# stm32.net
KiCad netlist of a schematic drawn in EAGLE
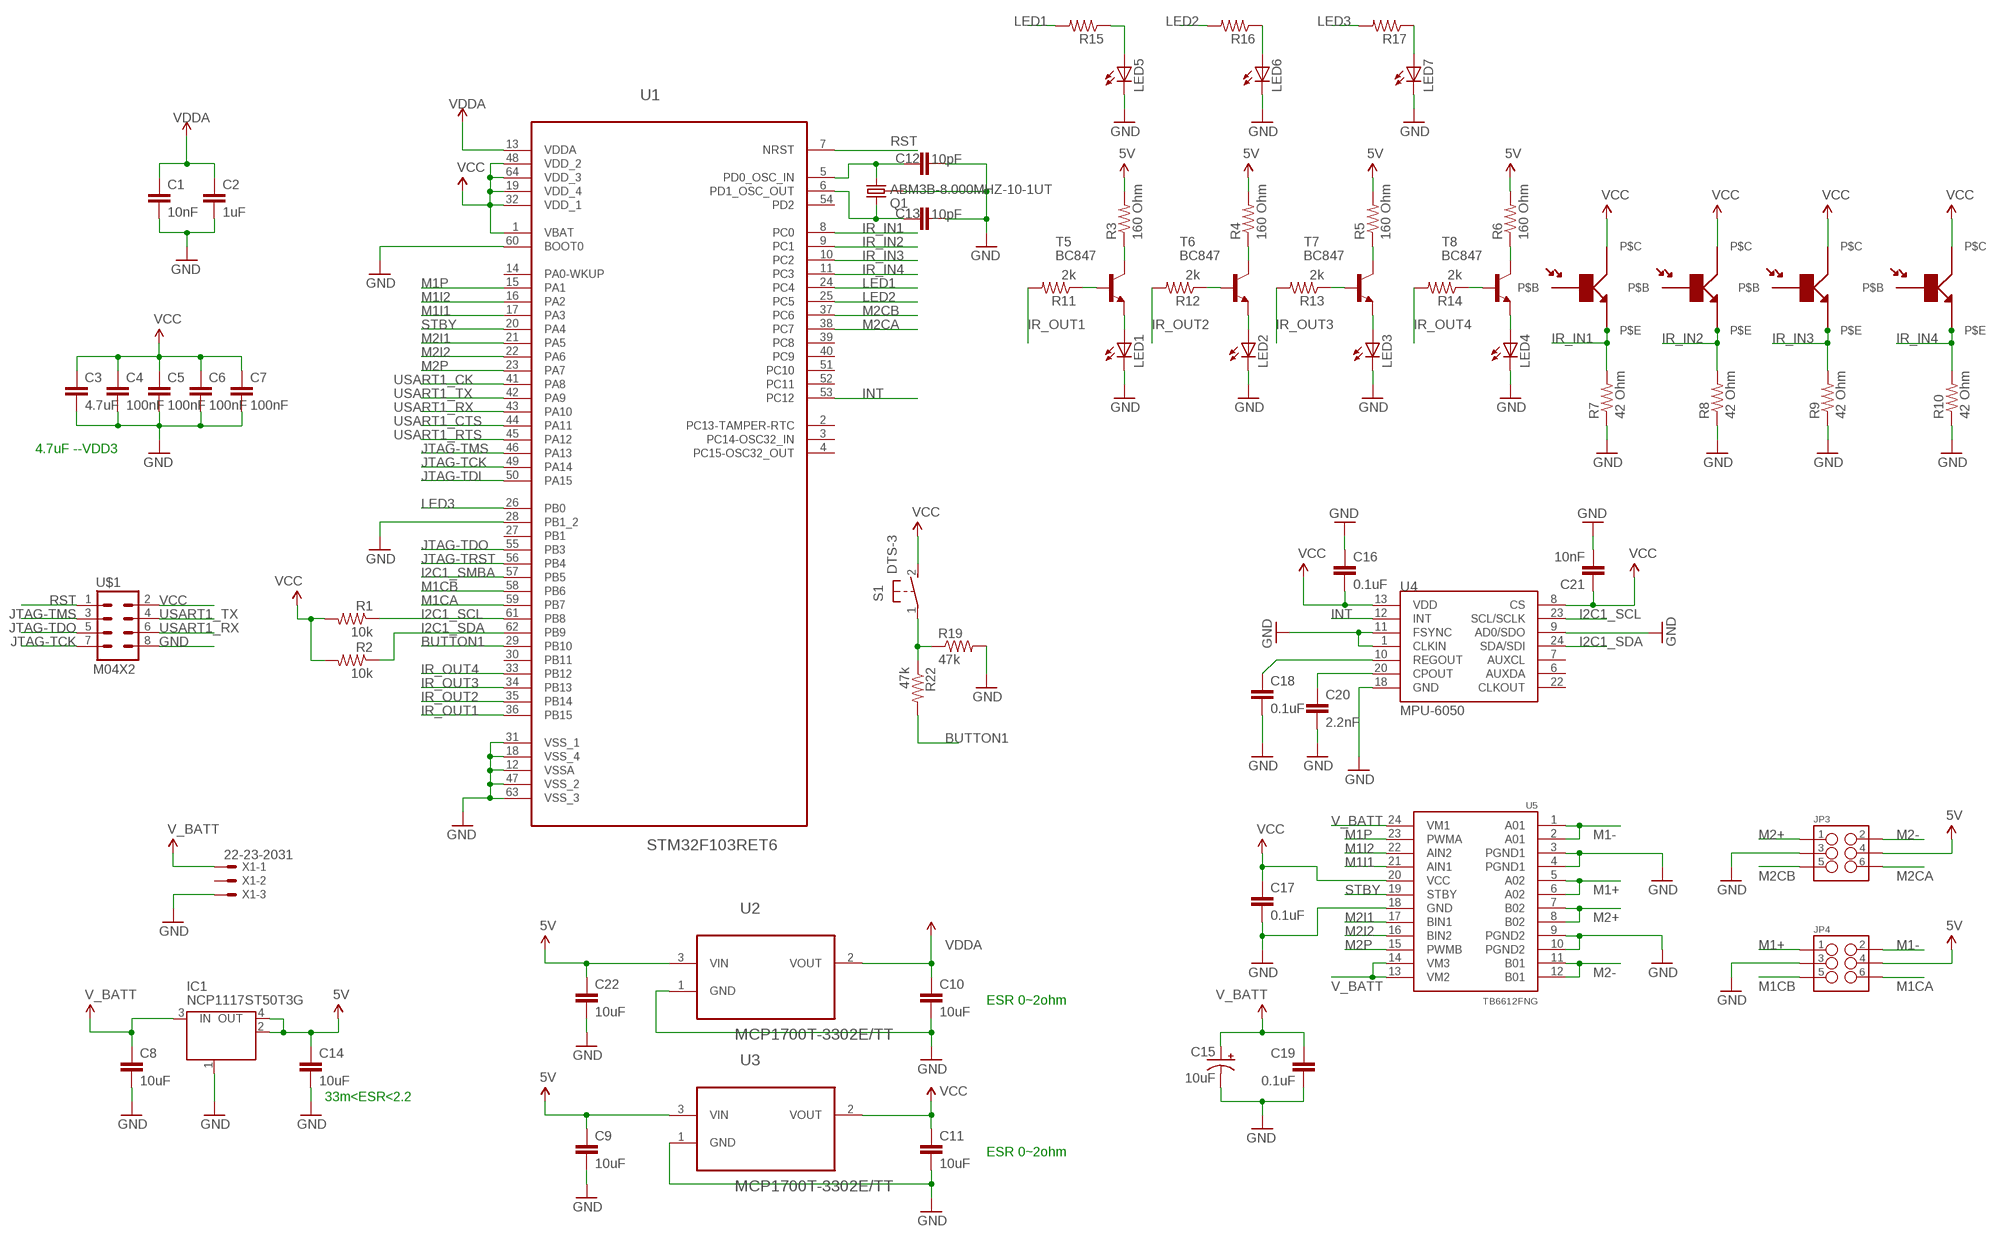
[diagram p0: schematic, sheet 1]

(export (version "E")
  (design (tool "Eeschema 10.0.6"))
  (components
    (comp (ref "C1")
      (value "10nF")
      (footprint "eagle-import:0805")
      (libsource (lib "eagle-import") (part "CAP0805"))
    )
    (comp (ref "C2")
      (value "1uF")
      (footprint "eagle-import:0805")
      (libsource (lib "eagle-import") (part "CAP0805"))
    )
    (comp (ref "C3")
      (value "4.7uF")
      (footprint "eagle-import:0805")
      (libsource (lib "eagle-import") (part "CAP0805"))
    )
    (comp (ref "C4")
      (value "100nF")
      (footprint "eagle-import:0805")
      (libsource (lib "eagle-import") (part "CAP0805"))
    )
    (comp (ref "C5")
      (value "100nF")
      (footprint "eagle-import:0805")
      (libsource (lib "eagle-import") (part "CAP0805"))
    )
    (comp (ref "C6")
      (value "100nF")
      (footprint "eagle-import:0805")
      (libsource (lib "eagle-import") (part "CAP0805"))
    )
    (comp (ref "C7")
      (value "100nF")
      (footprint "eagle-import:0805")
      (libsource (lib "eagle-import") (part "CAP0805"))
    )
    (comp (ref "C8")
      (value "10uF")
      (footprint "eagle-import:0805")
      (libsource (lib "eagle-import") (part "CAP0805"))
    )
    (comp (ref "C9")
      (value "10uF")
      (footprint "eagle-import:0805")
      (libsource (lib "eagle-import") (part "CAP0805"))
    )
    (comp (ref "C10")
      (value "10uF")
      (footprint "eagle-import:0805")
      (libsource (lib "eagle-import") (part "CAP0805"))
    )
    (comp (ref "C11")
      (value "10uF")
      (footprint "eagle-import:0805")
      (libsource (lib "eagle-import") (part "CAP0805"))
    )
    (comp (ref "C12")
      (value "10pF")
      (footprint "eagle-import:0805")
      (libsource (lib "eagle-import") (part "CAP0805"))
    )
    (comp (ref "C13")
      (value "10pF")
      (footprint "eagle-import:0805")
      (libsource (lib "eagle-import") (part "CAP0805"))
    )
    (comp (ref "C14")
      (value "10uF")
      (footprint "eagle-import:0805")
      (libsource (lib "eagle-import") (part "CAP0805"))
    )
    (comp (ref "C15")
      (value "10uF")
      (footprint "eagle-import:EIA3216-KIT")
      (libsource (lib "eagle-import") (part "CAP_POL1206-KIT"))
    )
    (comp (ref "C16")
      (value "0.1uF")
      (footprint "eagle-import:0805")
      (libsource (lib "eagle-import") (part "CAP0805"))
    )
    (comp (ref "C17")
      (value "0.1uF")
      (footprint "eagle-import:0805")
      (libsource (lib "eagle-import") (part "CAP0805"))
    )
    (comp (ref "C18")
      (value "0.1uF")
      (footprint "eagle-import:0805")
      (libsource (lib "eagle-import") (part "CAP0805"))
    )
    (comp (ref "C19")
      (value "0.1uF")
      (footprint "eagle-import:0805")
      (libsource (lib "eagle-import") (part "CAP0805"))
    )
    (comp (ref "C20")
      (value "2.2nF")
      (footprint "eagle-import:0805")
      (libsource (lib "eagle-import") (part "CAP0805"))
    )
    (comp (ref "C21")
      (value "10nF")
      (footprint "eagle-import:0805")
      (libsource (lib "eagle-import") (part "CAP0805"))
    )
    (comp (ref "C22")
      (value "10uF")
      (footprint "eagle-import:0805")
      (libsource (lib "eagle-import") (part "CAP0805"))
    )
    (comp (ref "IC1")
      (value "NCP1117ST50T3G")
      (footprint "eagle-import:SOT223")
      (libsource (lib "eagle-import") (part "MC33269ST-3.3T3"))
    )
    (comp (ref "JP3")
      (value "M03X2NO_SILK")
      (footprint "eagle-import:2X3-NS")
      (libsource (lib "eagle-import") (part "M03X2NO_SILK"))
    )
    (comp (ref "JP4")
      (value "M03X2NO_SILK")
      (footprint "eagle-import:2X3-NS")
      (libsource (lib "eagle-import") (part "M03X2NO_SILK"))
    )
    (comp (ref "LED1")
      (value "LED5MM")
      (footprint "eagle-import:LED5MM")
      (libsource (lib "eagle-import") (part "LED5MM"))
    )
    (comp (ref "LED2")
      (value "LED5MM")
      (footprint "eagle-import:LED5MM")
      (libsource (lib "eagle-import") (part "LED5MM"))
    )
    (comp (ref "LED3")
      (value "LED5MM")
      (footprint "eagle-import:LED5MM")
      (libsource (lib "eagle-import") (part "LED5MM"))
    )
    (comp (ref "LED4")
      (value "LED5MM")
      (footprint "eagle-import:LED5MM")
      (libsource (lib "eagle-import") (part "LED5MM"))
    )
    (comp (ref "LED5")
      (value "LEDSML0805")
      (footprint "eagle-import:SML0805")
      (libsource (lib "eagle-import") (part "LEDSML0805"))
    )
    (comp (ref "LED6")
      (value "LEDSML0805")
      (footprint "eagle-import:SML0805")
      (libsource (lib "eagle-import") (part "LEDSML0805"))
    )
    (comp (ref "LED7")
      (value "LEDSML0805")
      (footprint "eagle-import:SML0805")
      (libsource (lib "eagle-import") (part "LEDSML0805"))
    )
    (comp (ref "Q1")
      (value "ABM3B-8.000MHZ-10-1UT")
      (footprint "eagle-import:CRYSTAL-SMD-5X3")
      (libsource (lib "eagle-import") (part "CRYSTAL-GROUNDED"))
    )
    (comp (ref "R1")
      (value "10k")
      (footprint "eagle-import:0805")
      (libsource (lib "eagle-import") (part "RESISTOR0805-RES"))
    )
    (comp (ref "R2")
      (value "10k")
      (footprint "eagle-import:0805")
      (libsource (lib "eagle-import") (part "RESISTOR0805-RES"))
    )
    (comp (ref "R3")
      (value "160 Ohm")
      (footprint "eagle-import:0805")
      (libsource (lib "eagle-import") (part "SparkFun-Resistors_RESISTOR0805-RES"))
    )
    (comp (ref "R4")
      (value "160 Ohm")
      (footprint "eagle-import:0805")
      (libsource (lib "eagle-import") (part "SparkFun-Resistors_RESISTOR0805-RES"))
    )
    (comp (ref "R5")
      (value "160 Ohm")
      (footprint "eagle-import:0805")
      (libsource (lib "eagle-import") (part "SparkFun-Resistors_RESISTOR0805-RES"))
    )
    (comp (ref "R6")
      (value "160 Ohm")
      (footprint "eagle-import:0805")
      (libsource (lib "eagle-import") (part "SparkFun-Resistors_RESISTOR0805-RES"))
    )
    (comp (ref "R7")
      (value "42 Ohm")
      (footprint "eagle-import:0805")
      (libsource (lib "eagle-import") (part "SparkFun-Resistors_RESISTOR0805-RES"))
    )
    (comp (ref "R8")
      (value "42 Ohm")
      (footprint "eagle-import:0805")
      (libsource (lib "eagle-import") (part "SparkFun-Resistors_RESISTOR0805-RES"))
    )
    (comp (ref "R9")
      (value "42 Ohm")
      (footprint "eagle-import:0805")
      (libsource (lib "eagle-import") (part "SparkFun-Resistors_RESISTOR0805-RES"))
    )
    (comp (ref "R10")
      (value "42 Ohm")
      (footprint "eagle-import:0805")
      (libsource (lib "eagle-import") (part "SparkFun-Resistors_RESISTOR0805-RES"))
    )
    (comp (ref "R11")
      (value "2k")
      (footprint "eagle-import:0805")
      (libsource (lib "eagle-import") (part "SparkFun-Resistors_RESISTOR0805-RES"))
    )
    (comp (ref "R12")
      (value "2k")
      (footprint "eagle-import:0805")
      (libsource (lib "eagle-import") (part "SparkFun-Resistors_RESISTOR0805-RES"))
    )
    (comp (ref "R13")
      (value "2k")
      (footprint "eagle-import:0805")
      (libsource (lib "eagle-import") (part "SparkFun-Resistors_RESISTOR0805-RES"))
    )
    (comp (ref "R14")
      (value "2k")
      (footprint "eagle-import:0805")
      (libsource (lib "eagle-import") (part "SparkFun-Resistors_RESISTOR0805-RES"))
    )
    (comp (ref "R15")
      (value "RESISTOR0805-RES")
      (footprint "eagle-import:0805")
      (libsource (lib "eagle-import") (part "SparkFun-Resistors_RESISTOR0805-RES"))
    )
    (comp (ref "R16")
      (value "RESISTOR0805-RES")
      (footprint "eagle-import:0805")
      (libsource (lib "eagle-import") (part "SparkFun-Resistors_RESISTOR0805-RES"))
    )
    (comp (ref "R17")
      (value "RESISTOR0805-RES")
      (footprint "eagle-import:0805")
      (libsource (lib "eagle-import") (part "SparkFun-Resistors_RESISTOR0805-RES"))
    )
    (comp (ref "R19")
      (value "47k")
      (footprint "eagle-import:0805")
      (libsource (lib "eagle-import") (part "SparkFun-Resistors_RESISTOR0805-RES"))
    )
    (comp (ref "R22")
      (value "47k")
      (footprint "eagle-import:0805")
      (libsource (lib "eagle-import") (part "SparkFun-Resistors_RESISTOR0805-RES"))
    )
    (comp (ref "S1")
      (value "DTS-3")
      (footprint "eagle-import:DTS-3")
      (libsource (lib "eagle-import") (part "DTS-3"))
    )
    (comp (ref "T5")
      (value "BC847")
      (footprint "eagle-import:SOT23")
      (libsource (lib "eagle-import") (part "BC847"))
    )
    (comp (ref "T6")
      (value "BC847")
      (footprint "eagle-import:SOT23")
      (libsource (lib "eagle-import") (part "BC847"))
    )
    (comp (ref "T7")
      (value "BC847")
      (footprint "eagle-import:SOT23")
      (libsource (lib "eagle-import") (part "BC847"))
    )
    (comp (ref "T8")
      (value "BC847")
      (footprint "eagle-import:SOT23")
      (libsource (lib "eagle-import") (part "BC847"))
    )
    (comp (ref "U$1")
      (value "M04X2")
      (footprint "eagle-import:2X4")
      (libsource (lib "eagle-import") (part "M04X2"))
    )
    (comp (ref "U$2")
      (value "PHTRST")
      (footprint "eagle-import:PHTRST")
      (libsource (lib "eagle-import") (part "PHTRST"))
    )
    (comp (ref "U$3")
      (value "PHTRST")
      (footprint "eagle-import:PHTRST")
      (libsource (lib "eagle-import") (part "PHTRST"))
    )
    (comp (ref "U$4")
      (value "PHTRST")
      (footprint "eagle-import:PHTRST")
      (libsource (lib "eagle-import") (part "PHTRST"))
    )
    (comp (ref "U$5")
      (value "PHTRST")
      (footprint "eagle-import:PHTRST")
      (libsource (lib "eagle-import") (part "PHTRST"))
    )
    (comp (ref "U1")
      (value "STM32F103RET6")
      (footprint "eagle-import:QFP50P1200X1200X160-64N")
      (libsource (lib "eagle-import") (part "STM32F103RET6"))
    )
    (comp (ref "U2")
      (value "MCP1700T-3302E/TT")
      (footprint "eagle-import:SOT95P237X112-3N")
      (libsource (lib "eagle-import") (part "MCP1700T-3302E/TT"))
    )
    (comp (ref "U3")
      (value "MCP1700T-3302E/TT")
      (footprint "eagle-import:SOT95P237X112-3N")
      (libsource (lib "eagle-import") (part "MCP1700T-3302E/TT"))
    )
    (comp (ref "U4")
      (value "MPU-6050")
      (footprint "eagle-import:QFN-24-TESTING")
      (libsource (lib "eagle-import") (part "MPU-6000QFN-24"))
    )
    (comp (ref "U5")
      (value "TB6612FNG")
      (footprint "eagle-import:SSOP24")
      (libsource (lib "eagle-import") (part "TB6612FNG"))
    )
    (comp (ref "X1")
      (value "22-23-2031")
      (footprint "eagle-import:22-23-2031")
      (libsource (lib "eagle-import") (part "22-23-2031"))
    )
  )
  (nets
    (net (code "1") (name "/BUTTON1") (class "Default")
      (node (ref "R22") (pin "2") (pinfunction "2_2") (pintype "passive"))
      (node (ref "U1") (pin "29") (pinfunction "PB10_29") (pintype "bidirectional"))
    )
    (net (code "2") (name "/I2C1_SCL") (class "Default")
      (node (ref "R1") (pin "1") (pinfunction "1_1") (pintype "passive"))
      (node (ref "U1") (pin "61") (pinfunction "PB8_61") (pintype "bidirectional"))
      (node (ref "U4") (pin "23") (pinfunction "SCL/SCLK_23") (pintype "bidirectional"))
    )
    (net (code "3") (name "/I2C1_SDA") (class "Default")
      (node (ref "R2") (pin "1") (pinfunction "1_1") (pintype "passive"))
      (node (ref "U1") (pin "62") (pinfunction "PB9_62") (pintype "bidirectional"))
      (node (ref "U4") (pin "24") (pinfunction "SDA/SDI_24") (pintype "bidirectional"))
    )
    (net (code "4") (name "/I2C1_SMBA") (class "Default")
      (node (ref "U1") (pin "57") (pinfunction "PB5_57") (pintype "bidirectional"))
    )
    (net (code "5") (name "/INT") (class "Default")
      (node (ref "U1") (pin "53") (pinfunction "PC12_53") (pintype "bidirectional"))
      (node (ref "U4") (pin "12") (pinfunction "INT_12") (pintype "bidirectional"))
    )
    (net (code "6") (name "/IR_IN1") (class "Default")
      (node (ref "R7") (pin "2") (pinfunction "2_2") (pintype "passive"))
      (node (ref "U$2") (pin "P$E") (pinfunction "P$E_P$E") (pintype "bidirectional"))
      (node (ref "U1") (pin "8") (pinfunction "PC0_8") (pintype "bidirectional"))
    )
    (net (code "7") (name "/IR_IN2") (class "Default")
      (node (ref "R8") (pin "2") (pinfunction "2_2") (pintype "passive"))
      (node (ref "U$3") (pin "P$E") (pinfunction "P$E_P$E") (pintype "bidirectional"))
      (node (ref "U1") (pin "9") (pinfunction "PC1_9") (pintype "bidirectional"))
    )
    (net (code "8") (name "/IR_IN3") (class "Default")
      (node (ref "R9") (pin "2") (pinfunction "2_2") (pintype "passive"))
      (node (ref "U$4") (pin "P$E") (pinfunction "P$E_P$E") (pintype "bidirectional"))
      (node (ref "U1") (pin "10") (pinfunction "PC2_10") (pintype "bidirectional"))
    )
    (net (code "9") (name "/IR_IN4") (class "Default")
      (node (ref "R10") (pin "2") (pinfunction "2_2") (pintype "passive"))
      (node (ref "U$5") (pin "P$E") (pinfunction "P$E_P$E") (pintype "bidirectional"))
      (node (ref "U1") (pin "11") (pinfunction "PC3_11") (pintype "bidirectional"))
    )
    (net (code "10") (name "/IR_OUT1") (class "Default")
      (node (ref "R11") (pin "2") (pinfunction "2_2") (pintype "passive"))
      (node (ref "U1") (pin "36") (pinfunction "PB15_36") (pintype "bidirectional"))
    )
    (net (code "11") (name "/IR_OUT2") (class "Default")
      (node (ref "R12") (pin "2") (pinfunction "2_2") (pintype "passive"))
      (node (ref "U1") (pin "35") (pinfunction "PB14_35") (pintype "bidirectional"))
    )
    (net (code "12") (name "/IR_OUT3") (class "Default")
      (node (ref "R13") (pin "2") (pinfunction "2_2") (pintype "passive"))
      (node (ref "U1") (pin "34") (pinfunction "PB13_34") (pintype "bidirectional"))
    )
    (net (code "13") (name "/IR_OUT4") (class "Default")
      (node (ref "R14") (pin "2") (pinfunction "2_2") (pintype "passive"))
      (node (ref "U1") (pin "33") (pinfunction "PB12_33") (pintype "bidirectional"))
    )
    (net (code "14") (name "/JTAG-TCK") (class "Default")
      (node (ref "U$1") (pin "7") (pinfunction "7_7") (pintype "passive"))
      (node (ref "U1") (pin "49") (pinfunction "PA14_49") (pintype "bidirectional"))
    )
    (net (code "15") (name "/JTAG-TDI") (class "Default")
      (node (ref "U1") (pin "50") (pinfunction "PA15_50") (pintype "bidirectional"))
    )
    (net (code "16") (name "/JTAG-TDO") (class "Default")
      (node (ref "U$1") (pin "5") (pinfunction "5_5") (pintype "passive"))
      (node (ref "U1") (pin "55") (pinfunction "PB3_55") (pintype "bidirectional"))
    )
    (net (code "17") (name "/JTAG-TMS") (class "Default")
      (node (ref "U$1") (pin "3") (pinfunction "3_3") (pintype "passive"))
      (node (ref "U1") (pin "46") (pinfunction "PA13_46") (pintype "bidirectional"))
    )
    (net (code "18") (name "/JTAG-TRST") (class "Default")
      (node (ref "U1") (pin "56") (pinfunction "PB4_56") (pintype "bidirectional"))
    )
    (net (code "19") (name "/LED1") (class "Default")
      (node (ref "R15") (pin "2") (pinfunction "2_2") (pintype "passive"))
      (node (ref "U1") (pin "24") (pinfunction "PC4_24") (pintype "passive"))
    )
    (net (code "20") (name "/LED2") (class "Default")
      (node (ref "R16") (pin "2") (pinfunction "2_2") (pintype "passive"))
      (node (ref "U1") (pin "25") (pinfunction "PC5_25") (pintype "bidirectional"))
    )
    (net (code "21") (name "/LED3") (class "Default")
      (node (ref "R17") (pin "2") (pinfunction "2_2") (pintype "passive"))
      (node (ref "U1") (pin "26") (pinfunction "PB0_26") (pintype "bidirectional"))
    )
    (net (code "22") (name "/M1+") (class "Default")
      (node (ref "JP4") (pin "1") (pinfunction "1_1") (pintype "bidirectional"))
      (node (ref "U5") (pin "5") (pinfunction "A02_5") (pintype "bidirectional"))
      (node (ref "U5") (pin "6") (pinfunction "A02_6") (pintype "bidirectional"))
    )
    (net (code "23") (name "/M1-") (class "Default")
      (node (ref "JP4") (pin "2") (pinfunction "2_2") (pintype "bidirectional"))
      (node (ref "U5") (pin "1") (pinfunction "A01_1") (pintype "bidirectional"))
      (node (ref "U5") (pin "2") (pinfunction "A01_2") (pintype "bidirectional"))
    )
    (net (code "24") (name "/M1CA") (class "Default")
      (node (ref "JP4") (pin "6") (pinfunction "6_6") (pintype "bidirectional"))
      (node (ref "U1") (pin "59") (pinfunction "PB7_59") (pintype "power_in"))
    )
    (net (code "25") (name "/M1CB") (class "Default")
      (node (ref "JP4") (pin "5") (pinfunction "5_5") (pintype "bidirectional"))
      (node (ref "U1") (pin "58") (pinfunction "PB6_58") (pintype "bidirectional"))
    )
    (net (code "26") (name "/M1I1") (class "Default")
      (node (ref "U1") (pin "17") (pinfunction "PA3_17") (pintype "bidirectional"))
      (node (ref "U5") (pin "21") (pinfunction "AIN1_21") (pintype "bidirectional"))
    )
    (net (code "27") (name "/M1I2") (class "Default")
      (node (ref "U1") (pin "16") (pinfunction "PA2_16") (pintype "bidirectional"))
      (node (ref "U5") (pin "22") (pinfunction "AIN2_22") (pintype "bidirectional"))
    )
    (net (code "28") (name "/M1P") (class "Default")
      (node (ref "U1") (pin "15") (pinfunction "PA1_15") (pintype "bidirectional"))
      (node (ref "U5") (pin "23") (pinfunction "PWMA_23") (pintype "bidirectional"))
    )
    (net (code "29") (name "/M2+") (class "Default")
      (node (ref "JP3") (pin "1") (pinfunction "1_1") (pintype "bidirectional"))
      (node (ref "U5") (pin "7") (pinfunction "B02_7") (pintype "bidirectional"))
      (node (ref "U5") (pin "8") (pinfunction "B02_8") (pintype "bidirectional"))
    )
    (net (code "30") (name "/M2-") (class "Default")
      (node (ref "JP3") (pin "2") (pinfunction "2_2") (pintype "bidirectional"))
      (node (ref "U5") (pin "11") (pinfunction "B01_11") (pintype "bidirectional"))
      (node (ref "U5") (pin "12") (pinfunction "B01_12") (pintype "bidirectional"))
    )
    (net (code "31") (name "/M2CA") (class "Default")
      (node (ref "JP3") (pin "6") (pinfunction "6_6") (pintype "bidirectional"))
      (node (ref "U1") (pin "38") (pinfunction "PC7_38") (pintype "bidirectional"))
    )
    (net (code "32") (name "/M2CB") (class "Default")
      (node (ref "JP3") (pin "5") (pinfunction "5_5") (pintype "bidirectional"))
      (node (ref "U1") (pin "37") (pinfunction "PC6_37") (pintype "bidirectional"))
    )
    (net (code "33") (name "/M2I1") (class "Default")
      (node (ref "U1") (pin "21") (pinfunction "PA5_21") (pintype "bidirectional"))
      (node (ref "U5") (pin "17") (pinfunction "BIN1_17") (pintype "bidirectional"))
    )
    (net (code "34") (name "/M2I2") (class "Default")
      (node (ref "U1") (pin "22") (pinfunction "PA6_22") (pintype "bidirectional"))
      (node (ref "U5") (pin "16") (pinfunction "BIN2_16") (pintype "bidirectional"))
    )
    (net (code "35") (name "/M2P") (class "Default")
      (node (ref "U1") (pin "23") (pinfunction "PA7_23") (pintype "power_in"))
      (node (ref "U5") (pin "15") (pinfunction "PWMB_15") (pintype "bidirectional"))
    )
    (net (code "36") (name "/RST") (class "Default")
      (node (ref "U$1") (pin "1") (pinfunction "1_1") (pintype "passive"))
      (node (ref "U1") (pin "7") (pinfunction "NRST_7") (pintype "output"))
    )
    (net (code "37") (name "/STBY") (class "Default")
      (node (ref "U1") (pin "20") (pinfunction "PA4_20") (pintype "bidirectional"))
      (node (ref "U5") (pin "19") (pinfunction "STBY_19") (pintype "bidirectional"))
    )
    (net (code "38") (name "/USART1_CK") (class "Default")
      (node (ref "U1") (pin "41") (pinfunction "PA8_41") (pintype "bidirectional"))
    )
    (net (code "39") (name "/USART1_CTS") (class "Default")
      (node (ref "U1") (pin "44") (pinfunction "PA11_44") (pintype "bidirectional"))
    )
    (net (code "40") (name "/USART1_RTS") (class "Default")
      (node (ref "U1") (pin "45") (pinfunction "PA12_45") (pintype "bidirectional"))
    )
    (net (code "41") (name "/USART1_RX") (class "Default")
      (node (ref "U$1") (pin "6") (pinfunction "6_6") (pintype "passive"))
      (node (ref "U1") (pin "43") (pinfunction "PA10_43") (pintype "bidirectional"))
    )
    (net (code "42") (name "/USART1_TX") (class "Default")
      (node (ref "U$1") (pin "4") (pinfunction "4_4") (pintype "passive"))
      (node (ref "U1") (pin "42") (pinfunction "PA9_42") (pintype "bidirectional"))
    )
    (net (code "43") (name "5V") (class "Default")
      (node (ref "C14") (pin "1") (pinfunction "1_1") (pintype "passive"))
      (node (ref "C22") (pin "1") (pinfunction "1_1") (pintype "passive"))
      (node (ref "C9") (pin "1") (pinfunction "1_1") (pintype "passive"))
      (node (ref "IC1") (pin "2") (pinfunction "OUT_2") (pintype "passive"))
      (node (ref "IC1") (pin "4") (pinfunction "OUT_4") (pintype "passive"))
      (node (ref "JP3") (pin "4") (pinfunction "4_4") (pintype "bidirectional"))
      (node (ref "JP4") (pin "4") (pinfunction "4_4") (pintype "bidirectional"))
      (node (ref "R3") (pin "2") (pinfunction "2_2") (pintype "passive"))
      (node (ref "R4") (pin "2") (pinfunction "2_2") (pintype "passive"))
      (node (ref "R5") (pin "2") (pinfunction "2_2") (pintype "passive"))
      (node (ref "R6") (pin "2") (pinfunction "2_2") (pintype "passive"))
      (node (ref "U2") (pin "3") (pinfunction "VIN_3") (pintype "input"))
      (node (ref "U3") (pin "3") (pinfunction "VIN_3") (pintype "input"))
    )
    (net (code "44") (name "GND") (class "Default")
      (node (ref "C1") (pin "2") (pinfunction "2_2") (pintype "passive"))
      (node (ref "C10") (pin "2") (pinfunction "2_2") (pintype "passive"))
      (node (ref "C11") (pin "2") (pinfunction "2_2") (pintype "passive"))
      (node (ref "C12") (pin "1") (pinfunction "1_1") (pintype "passive"))
      (node (ref "C13") (pin "1") (pinfunction "1_1") (pintype "passive"))
      (node (ref "C14") (pin "2") (pinfunction "2_2") (pintype "passive"))
      (node (ref "C15") (pin "C") (pinfunction "-_C") (pintype "passive"))
      (node (ref "C16") (pin "1") (pinfunction "1_1") (pintype "passive"))
      (node (ref "C17") (pin "2") (pinfunction "2_2") (pintype "passive"))
      (node (ref "C18") (pin "2") (pinfunction "2_2") (pintype "passive"))
      (node (ref "C19") (pin "2") (pinfunction "2_2") (pintype "passive"))
      (node (ref "C2") (pin "2") (pinfunction "2_2") (pintype "passive"))
      (node (ref "C20") (pin "2") (pinfunction "2_2") (pintype "passive"))
      (node (ref "C21") (pin "2") (pinfunction "2_2") (pintype "passive"))
      (node (ref "C22") (pin "2") (pinfunction "2_2") (pintype "passive"))
      (node (ref "C3") (pin "2") (pinfunction "2_2") (pintype "passive"))
      (node (ref "C4") (pin "2") (pinfunction "2_2") (pintype "passive"))
      (node (ref "C5") (pin "2") (pinfunction "2_2") (pintype "passive"))
      (node (ref "C6") (pin "2") (pinfunction "2_2") (pintype "passive"))
      (node (ref "C7") (pin "2") (pinfunction "2_2") (pintype "passive"))
      (node (ref "C8") (pin "2") (pinfunction "2_2") (pintype "passive"))
      (node (ref "C9") (pin "2") (pinfunction "2_2") (pintype "passive"))
      (node (ref "IC1") (pin "1") (pinfunction "GND/ADJ_1") (pintype "input"))
      (node (ref "JP3") (pin "3") (pinfunction "3_3") (pintype "bidirectional"))
      (node (ref "JP4") (pin "3") (pinfunction "3_3") (pintype "bidirectional"))
      (node (ref "LED1") (pin "K") (pinfunction "C_K") (pintype "passive"))
      (node (ref "LED2") (pin "K") (pinfunction "C_K") (pintype "passive"))
      (node (ref "LED3") (pin "K") (pinfunction "C_K") (pintype "passive"))
      (node (ref "LED4") (pin "K") (pinfunction "C_K") (pintype "passive"))
      (node (ref "LED5") (pin "C") (pinfunction "C_C") (pintype "passive"))
      (node (ref "LED6") (pin "C") (pinfunction "C_C") (pintype "passive"))
      (node (ref "LED7") (pin "C") (pinfunction "C_C") (pintype "passive"))
      (node (ref "Q1") (pin "2") (pinfunction "3_2") (pintype "passive"))
      (node (ref "Q1") (pin "4") (pinfunction "3_4") (pintype "passive"))
      (node (ref "R10") (pin "1") (pinfunction "1_1") (pintype "passive"))
      (node (ref "R19") (pin "2") (pinfunction "2_2") (pintype "passive"))
      (node (ref "R7") (pin "1") (pinfunction "1_1") (pintype "passive"))
      (node (ref "R8") (pin "1") (pinfunction "1_1") (pintype "passive"))
      (node (ref "R9") (pin "1") (pinfunction "1_1") (pintype "passive"))
      (node (ref "U$1") (pin "8") (pinfunction "8_8") (pintype "passive"))
      (node (ref "U1") (pin "12") (pinfunction "VSSA_12") (pintype "passive"))
      (node (ref "U1") (pin "18") (pinfunction "VSS_4_18") (pintype "passive"))
      (node (ref "U1") (pin "28") (pinfunction "PB1_2_28") (pintype "bidirectional"))
      (node (ref "U1") (pin "31") (pinfunction "VSS_1_31") (pintype "passive"))
      (node (ref "U1") (pin "47") (pinfunction "VSS_2_47") (pintype "passive"))
      (node (ref "U1") (pin "60") (pinfunction "BOOT0_60") (pintype "passive"))
      (node (ref "U1") (pin "63") (pinfunction "VSS_3_63") (pintype "passive"))
      (node (ref "U2") (pin "1") (pinfunction "GND_1") (pintype "passive"))
      (node (ref "U3") (pin "1") (pinfunction "GND_1") (pintype "passive"))
      (node (ref "U4") (pin "1") (pinfunction "CLKIN_1") (pintype "bidirectional"))
      (node (ref "U4") (pin "11") (pinfunction "FSYNC_11") (pintype "bidirectional"))
      (node (ref "U4") (pin "18") (pinfunction "GND_18") (pintype "bidirectional"))
      (node (ref "U4") (pin "9") (pinfunction "AD0/SDO_9") (pintype "bidirectional"))
      (node (ref "U5") (pin "10") (pinfunction "PGND2_10") (pintype "bidirectional"))
      (node (ref "U5") (pin "18") (pinfunction "GND_18") (pintype "bidirectional"))
      (node (ref "U5") (pin "3") (pinfunction "PGND1_3") (pintype "bidirectional"))
      (node (ref "U5") (pin "4") (pinfunction "PGND1_4") (pintype "bidirectional"))
      (node (ref "U5") (pin "9") (pinfunction "PGND2_9") (pintype "bidirectional"))
      (node (ref "X1") (pin "3") (pinfunction "S_3") (pintype "passive"))
    )
    (net (code "45") (name "Net-(LED5-PadA)") (class "Default")
      (node (ref "LED5") (pin "A") (pinfunction "A_A") (pintype "passive"))
      (node (ref "R15") (pin "1") (pinfunction "1_1") (pintype "passive"))
    )
    (net (code "46") (name "Net-(LED6-PadA)") (class "Default")
      (node (ref "LED6") (pin "A") (pinfunction "A_A") (pintype "passive"))
      (node (ref "R16") (pin "1") (pinfunction "1_1") (pintype "passive"))
    )
    (net (code "47") (name "Net-(LED7-PadA)") (class "Default")
      (node (ref "LED7") (pin "A") (pinfunction "A_A") (pintype "passive"))
      (node (ref "R17") (pin "1") (pinfunction "1_1") (pintype "passive"))
    )
    (net (code "48") (name "Net-(Q1-1)") (class "Default")
      (node (ref "C12") (pin "2") (pinfunction "2_2") (pintype "passive"))
      (node (ref "Q1") (pin "3") (pinfunction "1_3") (pintype "passive"))
      (node (ref "U1") (pin "5") (pinfunction "PD0_OSC_IN_5") (pintype "input"))
    )
    (net (code "49") (name "Net-(Q1-2)") (class "Default")
      (node (ref "C13") (pin "2") (pinfunction "2_2") (pintype "passive"))
      (node (ref "Q1") (pin "1") (pinfunction "2_1") (pintype "passive"))
      (node (ref "U1") (pin "6") (pinfunction "PD1_OSC_OUT_6") (pintype "output"))
    )
    (net (code "50") (name "Net-(R19-Pad1)") (class "Default")
      (node (ref "R19") (pin "1") (pinfunction "1_1") (pintype "passive"))
      (node (ref "R22") (pin "1") (pinfunction "1_1") (pintype "passive"))
      (node (ref "S1") (pin "1") (pinfunction "1_1") (pintype "passive"))
    )
    (net (code "51") (name "Net-(T5-B)") (class "Default")
      (node (ref "R11") (pin "1") (pinfunction "1_1") (pintype "passive"))
      (node (ref "T5") (pin "1") (pinfunction "B_1") (pintype "passive"))
    )
    (net (code "52") (name "Net-(T5-C)") (class "Default")
      (node (ref "R3") (pin "1") (pinfunction "1_1") (pintype "passive"))
      (node (ref "T5") (pin "3") (pinfunction "C_3") (pintype "passive"))
    )
    (net (code "53") (name "Net-(T5-E)") (class "Default")
      (node (ref "LED1") (pin "A") (pinfunction "A_A") (pintype "passive"))
      (node (ref "T5") (pin "2") (pinfunction "E_2") (pintype "passive"))
    )
    (net (code "54") (name "Net-(T6-B)") (class "Default")
      (node (ref "R12") (pin "1") (pinfunction "1_1") (pintype "passive"))
      (node (ref "T6") (pin "1") (pinfunction "B_1") (pintype "passive"))
    )
    (net (code "55") (name "Net-(T6-C)") (class "Default")
      (node (ref "R4") (pin "1") (pinfunction "1_1") (pintype "passive"))
      (node (ref "T6") (pin "3") (pinfunction "C_3") (pintype "passive"))
    )
    (net (code "56") (name "Net-(T6-E)") (class "Default")
      (node (ref "LED2") (pin "A") (pinfunction "A_A") (pintype "passive"))
      (node (ref "T6") (pin "2") (pinfunction "E_2") (pintype "passive"))
    )
    (net (code "57") (name "Net-(T7-B)") (class "Default")
      (node (ref "R13") (pin "1") (pinfunction "1_1") (pintype "passive"))
      (node (ref "T7") (pin "1") (pinfunction "B_1") (pintype "passive"))
    )
    (net (code "58") (name "Net-(T7-C)") (class "Default")
      (node (ref "R5") (pin "1") (pinfunction "1_1") (pintype "passive"))
      (node (ref "T7") (pin "3") (pinfunction "C_3") (pintype "passive"))
    )
    (net (code "59") (name "Net-(T7-E)") (class "Default")
      (node (ref "LED3") (pin "A") (pinfunction "A_A") (pintype "passive"))
      (node (ref "T7") (pin "2") (pinfunction "E_2") (pintype "passive"))
    )
    (net (code "60") (name "Net-(T8-B)") (class "Default")
      (node (ref "R14") (pin "1") (pinfunction "1_1") (pintype "passive"))
      (node (ref "T8") (pin "1") (pinfunction "B_1") (pintype "passive"))
    )
    (net (code "61") (name "Net-(T8-C)") (class "Default")
      (node (ref "R6") (pin "1") (pinfunction "1_1") (pintype "passive"))
      (node (ref "T8") (pin "3") (pinfunction "C_3") (pintype "passive"))
    )
    (net (code "62") (name "Net-(T8-E)") (class "Default")
      (node (ref "LED4") (pin "A") (pinfunction "A_A") (pintype "passive"))
      (node (ref "T8") (pin "2") (pinfunction "E_2") (pintype "passive"))
    )
    (net (code "63") (name "Net-(U4-CPOUT)") (class "Default")
      (node (ref "C20") (pin "1") (pinfunction "1_1") (pintype "passive"))
      (node (ref "U4") (pin "20") (pinfunction "CPOUT_20") (pintype "bidirectional"))
    )
    (net (code "64") (name "Net-(U4-REGOUT)") (class "Default")
      (node (ref "C18") (pin "1") (pinfunction "1_1") (pintype "passive"))
      (node (ref "U4") (pin "10") (pinfunction "REGOUT_10") (pintype "bidirectional"))
    )
    (net (code "65") (name "VCC") (class "Default")
      (node (ref "C11") (pin "1") (pinfunction "1_1") (pintype "passive"))
      (node (ref "C16") (pin "2") (pinfunction "2_2") (pintype "passive"))
      (node (ref "C17") (pin "1") (pinfunction "1_1") (pintype "passive"))
      (node (ref "C21") (pin "1") (pinfunction "1_1") (pintype "passive"))
      (node (ref "C3") (pin "1") (pinfunction "1_1") (pintype "passive"))
      (node (ref "C4") (pin "1") (pinfunction "1_1") (pintype "passive"))
      (node (ref "C5") (pin "1") (pinfunction "1_1") (pintype "passive"))
      (node (ref "C6") (pin "1") (pinfunction "1_1") (pintype "passive"))
      (node (ref "C7") (pin "1") (pinfunction "1_1") (pintype "passive"))
      (node (ref "R1") (pin "2") (pinfunction "2_2") (pintype "passive"))
      (node (ref "R2") (pin "2") (pinfunction "2_2") (pintype "passive"))
      (node (ref "S1") (pin "2") (pinfunction "2_2") (pintype "passive"))
      (node (ref "U$1") (pin "2") (pinfunction "2_2") (pintype "passive"))
      (node (ref "U$2") (pin "P$C") (pinfunction "P$C_P$C") (pintype "bidirectional"))
      (node (ref "U$3") (pin "P$C") (pinfunction "P$C_P$C") (pintype "bidirectional"))
      (node (ref "U$4") (pin "P$C") (pinfunction "P$C_P$C") (pintype "bidirectional"))
      (node (ref "U$5") (pin "P$C") (pinfunction "P$C_P$C") (pintype "bidirectional"))
      (node (ref "U1") (pin "1") (pinfunction "VBAT_1") (pintype "input"))
      (node (ref "U1") (pin "19") (pinfunction "VDD_4_19") (pintype "power_in"))
      (node (ref "U1") (pin "32") (pinfunction "VDD_1_32") (pintype "power_in"))
      (node (ref "U1") (pin "48") (pinfunction "VDD_2_48") (pintype "power_in"))
      (node (ref "U1") (pin "64") (pinfunction "VDD_3_64") (pintype "power_in"))
      (node (ref "U3") (pin "2") (pinfunction "VOUT_2") (pintype "output"))
      (node (ref "U4") (pin "13") (pinfunction "VDD_13") (pintype "bidirectional"))
      (node (ref "U4") (pin "8") (pinfunction "CS_8") (pintype "bidirectional"))
      (node (ref "U5") (pin "20") (pinfunction "VCC_20") (pintype "bidirectional"))
    )
    (net (code "66") (name "VDDA") (class "Default")
      (node (ref "C1") (pin "1") (pinfunction "1_1") (pintype "passive"))
      (node (ref "C10") (pin "1") (pinfunction "1_1") (pintype "passive"))
      (node (ref "C2") (pin "1") (pinfunction "1_1") (pintype "passive"))
      (node (ref "U1") (pin "13") (pinfunction "VDDA_13") (pintype "power_in"))
      (node (ref "U2") (pin "2") (pinfunction "VOUT_2") (pintype "output"))
    )
    (net (code "67") (name "V_BATT") (class "Default")
      (node (ref "C15") (pin "A") (pinfunction "+_A") (pintype "passive"))
      (node (ref "C19") (pin "1") (pinfunction "1_1") (pintype "passive"))
      (node (ref "C8") (pin "1") (pinfunction "1_1") (pintype "passive"))
      (node (ref "IC1") (pin "3") (pinfunction "IN_3") (pintype "input"))
      (node (ref "U5") (pin "13") (pinfunction "VM2_13") (pintype "bidirectional"))
      (node (ref "U5") (pin "14") (pinfunction "VM3_14") (pintype "bidirectional"))
      (node (ref "U5") (pin "24") (pinfunction "VM1_24") (pintype "bidirectional"))
      (node (ref "X1") (pin "1") (pinfunction "S_1") (pintype "passive"))
    )
    (net (code "68") (name "unconnected-(U$2-PadP$B)") (class "Default")
      (node (ref "U$2") (pin "P$B") (pinfunction "P$B_P$B") (pintype "bidirectional"))
    )
    (net (code "69") (name "unconnected-(U$3-PadP$B)") (class "Default")
      (node (ref "U$3") (pin "P$B") (pinfunction "P$B_P$B") (pintype "bidirectional"))
    )
    (net (code "70") (name "unconnected-(U$4-PadP$B)") (class "Default")
      (node (ref "U$4") (pin "P$B") (pinfunction "P$B_P$B") (pintype "bidirectional"))
    )
    (net (code "71") (name "unconnected-(U$5-PadP$B)") (class "Default")
      (node (ref "U$5") (pin "P$B") (pinfunction "P$B_P$B") (pintype "bidirectional"))
    )
    (net (code "72") (name "unconnected-(U1-PA0-WKUP-Pad14)") (class "Default")
      (node (ref "U1") (pin "14") (pinfunction "PA0-WKUP_14") (pintype "bidirectional"))
    )
    (net (code "73") (name "unconnected-(U1-PB1-Pad27)") (class "Default")
      (node (ref "U1") (pin "27") (pinfunction "PB1_27") (pintype "bidirectional"))
    )
    (net (code "74") (name "unconnected-(U1-PB11-Pad30)") (class "Default")
      (node (ref "U1") (pin "30") (pinfunction "PB11_30") (pintype "bidirectional"))
    )
    (net (code "75") (name "unconnected-(U1-PC8-Pad39)") (class "Default")
      (node (ref "U1") (pin "39") (pinfunction "PC8_39") (pintype "bidirectional"))
    )
    (net (code "76") (name "unconnected-(U1-PC9-Pad40)") (class "Default")
      (node (ref "U1") (pin "40") (pinfunction "PC9_40") (pintype "bidirectional"))
    )
    (net (code "77") (name "unconnected-(U1-PC10-Pad51)") (class "Default")
      (node (ref "U1") (pin "51") (pinfunction "PC10_51") (pintype "bidirectional"))
    )
    (net (code "78") (name "unconnected-(U1-PC11-Pad52)") (class "Default")
      (node (ref "U1") (pin "52") (pinfunction "PC11_52") (pintype "bidirectional"))
    )
    (net (code "79") (name "unconnected-(U1-PC13-TAMPER-RTC-Pad2)") (class "Default")
      (node (ref "U1") (pin "2") (pinfunction "PC13-TAMPER-RTC_2") (pintype "input"))
    )
    (net (code "80") (name "unconnected-(U1-PC14-OSC32_IN-Pad3)") (class "Default")
      (node (ref "U1") (pin "3") (pinfunction "PC14-OSC32_IN_3") (pintype "input"))
    )
    (net (code "81") (name "unconnected-(U1-PC15-OSC32_OUT-Pad4)") (class "Default")
      (node (ref "U1") (pin "4") (pinfunction "PC15-OSC32_OUT_4") (pintype "output"))
    )
    (net (code "82") (name "unconnected-(U1-PD2-Pad54)") (class "Default")
      (node (ref "U1") (pin "54") (pinfunction "PD2_54") (pintype "bidirectional"))
    )
    (net (code "83") (name "unconnected-(U4-AUXCL-Pad7)") (class "Default")
      (node (ref "U4") (pin "7") (pinfunction "AUXCL_7") (pintype "bidirectional"))
    )
    (net (code "84") (name "unconnected-(U4-AUXDA-Pad6)") (class "Default")
      (node (ref "U4") (pin "6") (pinfunction "AUXDA_6") (pintype "bidirectional"))
    )
    (net (code "85") (name "unconnected-(U4-CLKOUT-Pad22)") (class "Default")
      (node (ref "U4") (pin "22") (pinfunction "CLKOUT_22") (pintype "bidirectional"))
    )
    (net (code "86") (name "unconnected-(X1B-S-Pad2)") (class "Default")
      (node (ref "X1") (pin "2") (pinfunction "S_2") (pintype "passive"))
    )
  )
)
